# Power_12V.net
KiCad netlist of a schematic drawn in Altium Designer
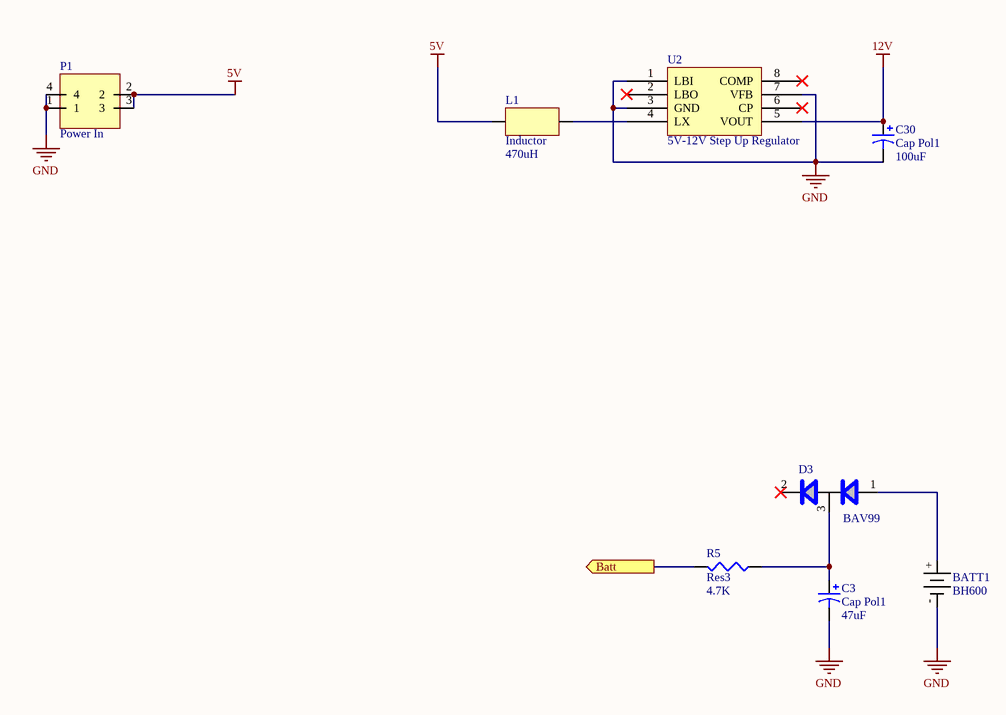
[diagram p0: Power_12V.SchDoc]

(export (version "E")
  (design (tool "Eeschema 10.0.6"))
  (components
    (comp (ref "BATT1")
      (value "BH600")
      (footprint "BH600")
      (description "16mm Battery Holder - Memory Protection Devices")
      (libsource (lib "CoinBatteryHolders") (part "BH600"))
    )
    (comp (ref "C3")
      (value "Cap Pol1")
      (footprint "CAPPR5-5x5")
      (description "Polarized Capacitor (Radial)")
      (fields (field (name "ALTIUM_VALUE") "47uF") (field (name "PUBLISHER") "Altium Limited"))
      (libsource (lib "Miscellaneous Devices") (part "Cap Pol1"))
    )
    (comp (ref "C30")
      (value "Cap Pol1")
      (footprint "CAPPR5-5x5")
      (description "Polarized Capacitor (Radial)")
      (fields (field (name "ALTIUM_VALUE") "100uF") (field (name "PUBLISHER") "Altium Limited"))
      (libsource (lib "Miscellaneous Devices") (part "Cap Pol1"))
    )
    (comp (ref "D3")
      (value "BAV99")
      (footprint "SOT23")
      (description "Dual Surface Mount Switching Diode")
      (libsource (lib "Diodes") (part "BAV99"))
    )
    (comp (ref "L1")
      (value "Inductor")
      (footprint "2120-RC")
      (fields (field (name "ALTIUM_VALUE") "470uH"))
      (libsource (lib "Bourns") (part "Component_1"))
    )
    (comp (ref "P1")
      (value "Power In")
      (footprint "Molex:0039300040 MINI-FIT JR 4-Pos Right Angle")
      (libsource (lib "Molex") (part "0039300040 Mini-Fit 2x2 Right Angle"))
    )
    (comp (ref "R5")
      (value "Res3")
      (footprint "J1-0603")
      (description "Resistor")
      (fields (field (name "ALTIUM_VALUE") "4.7K") (field (name "PUBLISHER") "Altium Limited"))
      (libsource (lib "Miscellaneous Devices") (part "Res3"))
    )
    (comp (ref "U2")
      (value "5V-12V Step Up Regulator")
      (footprint "DIP-8")
      (libsource (lib "KVM Mux") (part "MAX632"))
    )
  )
  (nets
    (net (code "1") (name "/Batt") (class "Default")
      (node (ref "R5") (pin "2") (pinfunction "2_2") (pintype "passive"))
    )
    (net (code "2") (name "5V") (class "Default")
      (node (ref "L1") (pin "1") (pinfunction "1_1") (pintype "passive"))
      (node (ref "P1") (pin "2") (pinfunction "2_2") (pintype "passive"))
      (node (ref "P1") (pin "3") (pinfunction "3_3") (pintype "passive"))
    )
    (net (code "3") (name "12V") (class "Default")
      (node (ref "C30") (pin "1") (pinfunction "1_1") (pintype "passive"))
      (node (ref "U2") (pin "5") (pinfunction "VOUT_5") (pintype "passive"))
    )
    (net (code "4") (name "GND") (class "Default")
      (node (ref "BATT1") (pin "-") (pinfunction "1_-") (pintype "passive"))
      (node (ref "C3") (pin "2") (pinfunction "2_2") (pintype "passive"))
      (node (ref "C30") (pin "2") (pinfunction "2_2") (pintype "passive"))
      (node (ref "P1") (pin "1") (pinfunction "1_1") (pintype "passive"))
      (node (ref "P1") (pin "4") (pinfunction "4_4") (pintype "passive"))
      (node (ref "U2") (pin "1") (pinfunction "LBI_1") (pintype "passive"))
      (node (ref "U2") (pin "3") (pinfunction "GND_3") (pintype "passive"))
      (node (ref "U2") (pin "7") (pinfunction "VFB_7") (pintype "passive"))
    )
    (net (code "5") (name "Net-(BATT1-0)") (class "Default")
      (node (ref "BATT1") (pin "+") (pinfunction "0_+") (pintype "passive"))
      (node (ref "D3") (pin "1") (pinfunction "1_1") (pintype "passive"))
    )
    (net (code "6") (name "Net-(C3-Pad1)") (class "Default")
      (node (ref "C3") (pin "1") (pinfunction "1_1") (pintype "passive"))
      (node (ref "D3") (pin "3") (pinfunction "3_3") (pintype "passive"))
      (node (ref "R5") (pin "1") (pinfunction "1_1") (pintype "passive"))
    )
    (net (code "7") (name "Net-(U2-LX)") (class "Default")
      (node (ref "L1") (pin "2") (pinfunction "2_2") (pintype "passive"))
      (node (ref "U2") (pin "4") (pinfunction "LX_4") (pintype "passive"))
    )
    (net (code "8") (name "unconnected-(D3-Pad2)") (class "Default")
      (node (ref "D3") (pin "2") (pinfunction "2_2") (pintype "passive+no_connect"))
    )
    (net (code "9") (name "unconnected-(U2-COMP-Pad8)") (class "Default")
      (node (ref "U2") (pin "8") (pinfunction "COMP_8") (pintype "passive+no_connect"))
    )
    (net (code "10") (name "unconnected-(U2-CP-Pad6)") (class "Default")
      (node (ref "U2") (pin "6") (pinfunction "CP_6") (pintype "passive+no_connect"))
    )
    (net (code "11") (name "unconnected-(U2-LBO-Pad2)") (class "Default")
      (node (ref "U2") (pin "2") (pinfunction "LBO_2") (pintype "passive+no_connect"))
    )
  )
)
